# esphome-lg-pqrcuds0-rev1.net
KiCad netlist of a schematic drawn in EAGLE
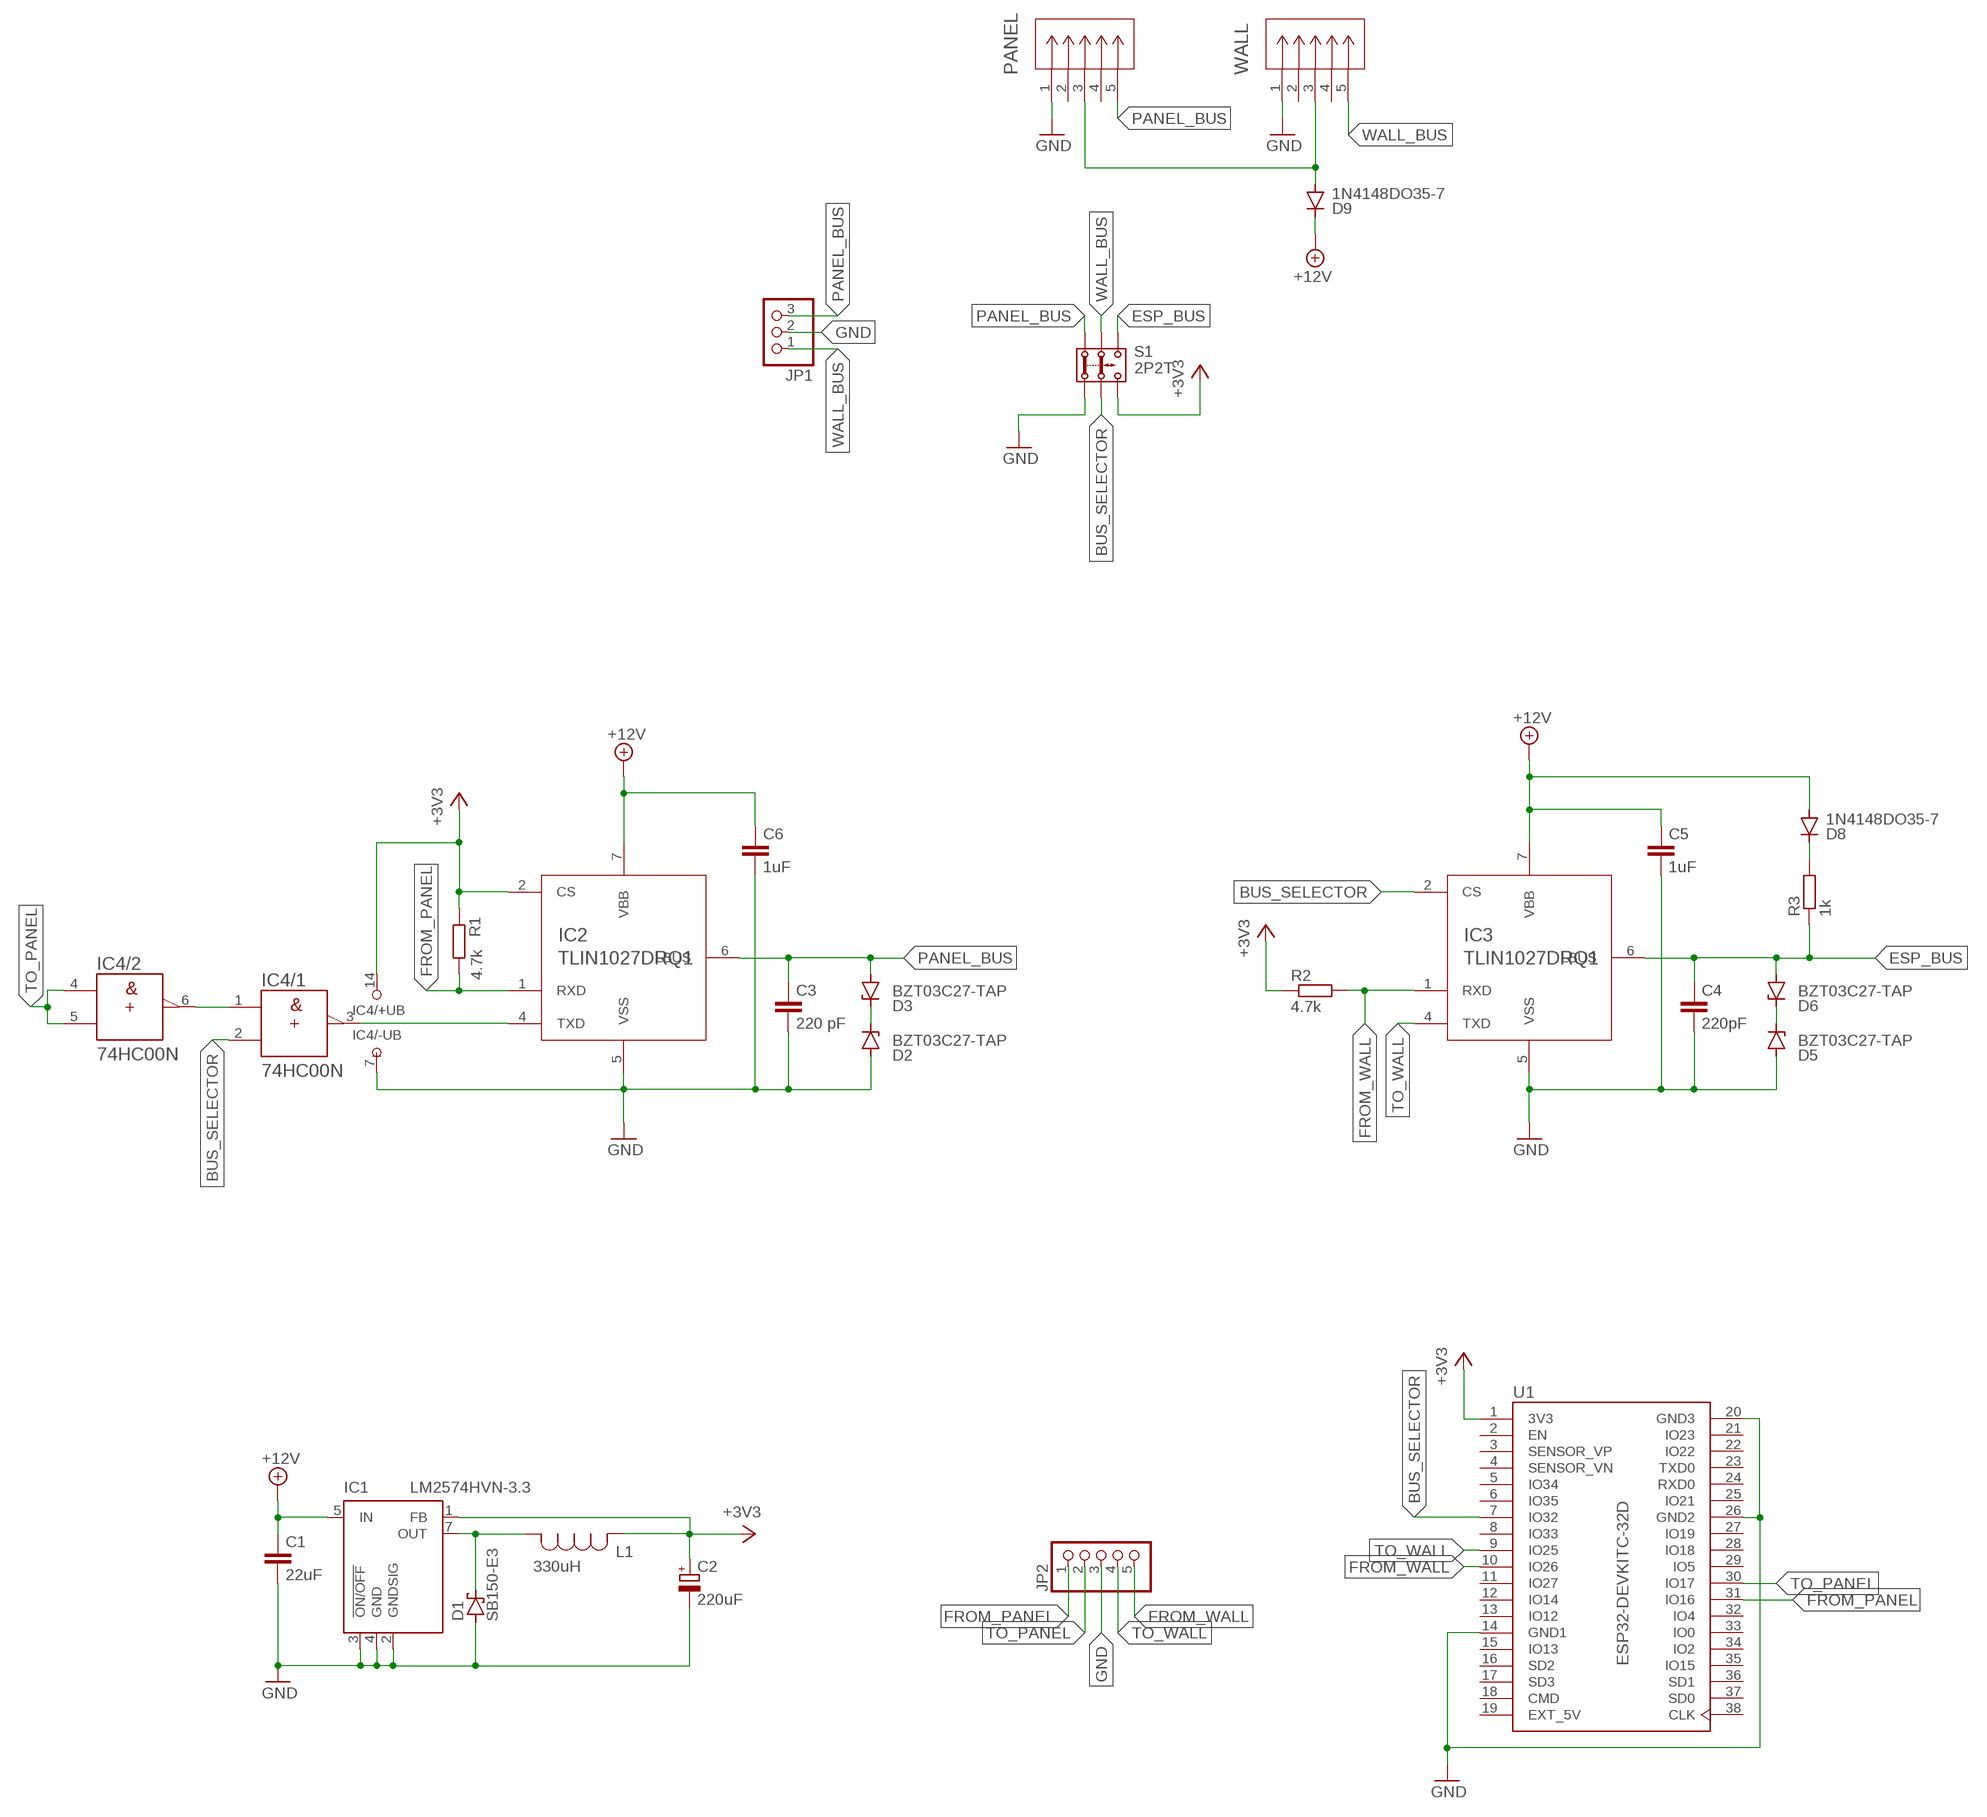
[diagram p0: schematic, sheet 1]

(export (version "E")
  (design (tool "Eeschema 10.0.6"))
  (components
    (comp (ref "C1")
      (value "22uF")
      (footprint "eagle-import:C050-025X075")
      (libsource (lib "eagle-import") (part "C-EU050-025X075"))
    )
    (comp (ref "C2")
      (value "220uF")
      (footprint "eagle-import:E2,5-6E")
      (libsource (lib "eagle-import") (part "CPOL-EUE2,5-6E"))
    )
    (comp (ref "C3")
      (value "220 pF")
      (footprint "eagle-import:C050-025X075")
      (libsource (lib "eagle-import") (part "C-EU050-025X075"))
    )
    (comp (ref "C4")
      (value "220pF")
      (footprint "eagle-import:C050-025X075")
      (libsource (lib "eagle-import") (part "C-EU050-025X075"))
    )
    (comp (ref "C5")
      (value "1uF")
      (footprint "eagle-import:C050-025X075")
      (libsource (lib "eagle-import") (part "C-EU050-025X075"))
    )
    (comp (ref "C6")
      (value "1uF")
      (footprint "eagle-import:C050-025X075")
      (libsource (lib "eagle-import") (part "C-EU050-025X075"))
    )
    (comp (ref "D1")
      (value "SB150-E3")
      (footprint "eagle-import:DO35-7")
      (libsource (lib "eagle-import") (part "SCHOTTKY-DIODEDO35-7"))
    )
    (comp (ref "D2")
      (value "BZT03C27-TAP")
      (footprint "eagle-import:SOD57Z10")
      (libsource (lib "eagle-import") (part "ZENER-DIODESOD57-10"))
    )
    (comp (ref "D3")
      (value "BZT03C27-TAP")
      (footprint "eagle-import:SOD57Z10")
      (libsource (lib "eagle-import") (part "ZENER-DIODESOD57-10"))
    )
    (comp (ref "D5")
      (value "BZT03C27-TAP")
      (footprint "eagle-import:SOD57Z10")
      (libsource (lib "eagle-import") (part "ZENER-DIODESOD57-10"))
    )
    (comp (ref "D6")
      (value "BZT03C27-TAP")
      (footprint "eagle-import:SOD57Z10")
      (libsource (lib "eagle-import") (part "ZENER-DIODESOD57-10"))
    )
    (comp (ref "D8")
      (value "1N4148DO35-7")
      (footprint "eagle-import:DO35-7")
      (libsource (lib "eagle-import") (part "1N4148DO35-7"))
    )
    (comp (ref "D9")
      (value "1N4148DO35-7")
      (footprint "eagle-import:DO35-7")
      (libsource (lib "eagle-import") (part "1N4148DO35-7"))
    )
    (comp (ref "IC1")
      (value "LM2574HVN-3.3")
      (footprint "eagle-import:DIL08")
      (libsource (lib "eagle-import") (part "LM2574?-HVN3.3"))
    )
    (comp (ref "IC2")
      (value "TLIN1027DRQ1")
      (footprint "eagle-import:SOIC8")
      (libsource (lib "eagle-import") (part "TLIN1027DRQ1"))
    )
    (comp (ref "IC3")
      (value "TLIN1027DRQ1")
      (footprint "eagle-import:SOIC8")
      (libsource (lib "eagle-import") (part "TLIN1027DRQ1"))
    )
    (comp (ref "IC4")
      (value "74HC00N")
      (footprint "eagle-import:DIL14")
      (libsource (lib "eagle-import") (part "7400NHC"))
    )
    (comp (ref "JP1")
      (value "PINHD-1X3/90")
      (footprint "eagle-import:1X03_90")
      (libsource (lib "eagle-import") (part "PINHD-1X3/90"))
    )
    (comp (ref "JP2")
      (value "PINHD-1X5/90")
      (footprint "eagle-import:1X05_90")
      (libsource (lib "eagle-import") (part "PINHD-1X5/90"))
    )
    (comp (ref "L1")
      (value "330uH")
      (footprint "eagle-import:AIAP-02_ABR")
      (fields (field (name "MANUFACTURER_PART_NUMBER") "AIAP-02-331K"))
      (libsource (lib "eagle-import") (part "AIAP-02-331K"))
    )
    (comp (ref "PANEL")
      (value "S5B-ZR(LF)(SN)")
      (footprint "eagle-import:CONN_S5B-ZR_JST")
      (fields (field (name "COPYRIGHT") "Copyright (C) 2018 Accelerated Designs. All rights reserved"))
      (libsource (lib "eagle-import") (part "S5B-ZR(LF)(SN)"))
    )
    (comp (ref "R1")
      (value "4.7k")
      (footprint "eagle-import:0204_7")
      (libsource (lib "eagle-import") (part "R-EU_0204/7"))
    )
    (comp (ref "R2")
      (value "4.7k")
      (footprint "eagle-import:0204_7")
      (libsource (lib "eagle-import") (part "R-EU_0204/7"))
    )
    (comp (ref "R3")
      (value "1k")
      (footprint "eagle-import:0204_7")
      (libsource (lib "eagle-import") (part "R-EU_0204/7"))
    )
    (comp (ref "S1")
      (value "2P2T")
      (footprint "eagle-import:2P2T")
      (libsource (lib "eagle-import") (part "2P2T"))
    )
    (comp (ref "U1")
      (value "ESP32-DEVKITC-32D")
      (footprint "eagle-import:MODULE_ESP32-DEVKITC-32D")
      (fields (field (name "MF") "Espressif Systems"))
      (libsource (lib "eagle-import") (part "ESP32-DEVKITC-32D"))
    )
    (comp (ref "WALL")
      (value "S5B-ZR(LF)(SN)")
      (footprint "eagle-import:CONN_S5B-ZR_JST")
      (fields (field (name "COPYRIGHT") "Copyright (C) 2018 Accelerated Designs. All rights reserved"))
      (libsource (lib "eagle-import") (part "S5B-ZR(LF)(SN)"))
    )
  )
  (nets
    (net (code "1") (name "+3V3") (class "Default")
      (node (ref "C2") (pin "+") (pinfunction "+_+") (pintype "passive"))
      (node (ref "IC1") (pin "1") (pinfunction "FB_1") (pintype "input"))
      (node (ref "IC2") (pin "2") (pinfunction "CS_2") (pintype "input"))
      (node (ref "IC4") (pin "14") (pinfunction "+UB_14") (pintype "power_in"))
      (node (ref "L1") (pin "2") (pinfunction "2_2") (pintype "passive"))
      (node (ref "R1") (pin "1") (pinfunction "1_1") (pintype "passive"))
      (node (ref "R2") (pin "1") (pinfunction "1_1") (pintype "passive"))
      (node (ref "S1") (pin "3.2") (pinfunction "3.2_3.2") (pintype "passive"))
      (node (ref "U1") (pin "1") (pinfunction "3V3_1") (pintype "power_in"))
    )
    (net (code "2") (name "+12V") (class "Default")
      (node (ref "C1") (pin "1") (pinfunction "1_1") (pintype "passive"))
      (node (ref "C5") (pin "1") (pinfunction "1_1") (pintype "passive"))
      (node (ref "C6") (pin "1") (pinfunction "1_1") (pintype "passive"))
      (node (ref "D8") (pin "A") (pinfunction "A_A") (pintype "passive"))
      (node (ref "D9") (pin "C") (pinfunction "C_C") (pintype "passive"))
      (node (ref "IC1") (pin "5") (pinfunction "IN_5") (pintype "input"))
      (node (ref "IC2") (pin "7") (pinfunction "VBB_7") (pintype "power_in"))
      (node (ref "IC3") (pin "7") (pinfunction "VBB_7") (pintype "power_in"))
    )
    (net (code "3") (name "/EXT_5V") (class "Default")
      (node (ref "U1") (pin "19") (pinfunction "EXT_5V_19") (pintype "power_in"))
    )
    (net (code "4") (name "BUS_SELECTOR") (class "Default")
      (node (ref "IC3") (pin "2") (pinfunction "CS_2") (pintype "input"))
      (node (ref "IC4") (pin "2") (pinfunction "B_2") (pintype "input"))
      (node (ref "S1") (pin "2.2") (pinfunction "2.2_2.2") (pintype "passive"))
      (node (ref "U1") (pin "7") (pinfunction "IO32_7") (pintype "bidirectional"))
    )
    (net (code "5") (name "ESP_BUS") (class "Default")
      (node (ref "C4") (pin "1") (pinfunction "1_1") (pintype "passive"))
      (node (ref "D6") (pin "A") (pinfunction "A_A") (pintype "passive"))
      (node (ref "IC3") (pin "6") (pinfunction "LBUS_6") (pintype "bidirectional"))
      (node (ref "R3") (pin "1") (pinfunction "1_1") (pintype "passive"))
      (node (ref "S1") (pin "3.1") (pinfunction "3.1_3.1") (pintype "passive"))
    )
    (net (code "6") (name "FROM_PANEL") (class "Default")
      (node (ref "IC2") (pin "1") (pinfunction "RXD_1") (pintype "output"))
      (node (ref "JP2") (pin "1") (pinfunction "1_1") (pintype "passive"))
      (node (ref "R1") (pin "2") (pinfunction "2_2") (pintype "passive"))
      (node (ref "U1") (pin "31") (pinfunction "IO16_31") (pintype "bidirectional"))
    )
    (net (code "7") (name "FROM_WALL") (class "Default")
      (node (ref "IC3") (pin "1") (pinfunction "RXD_1") (pintype "output"))
      (node (ref "JP2") (pin "5") (pinfunction "5_5") (pintype "passive"))
      (node (ref "R2") (pin "2") (pinfunction "2_2") (pintype "passive"))
      (node (ref "U1") (pin "10") (pinfunction "IO26_10") (pintype "bidirectional"))
    )
    (net (code "8") (name "GND") (class "Default")
      (node (ref "C1") (pin "2") (pinfunction "2_2") (pintype "passive"))
      (node (ref "C2") (pin "-") (pinfunction "-_-") (pintype "passive"))
      (node (ref "C3") (pin "2") (pinfunction "2_2") (pintype "passive"))
      (node (ref "C4") (pin "2") (pinfunction "2_2") (pintype "passive"))
      (node (ref "C5") (pin "2") (pinfunction "2_2") (pintype "passive"))
      (node (ref "C6") (pin "2") (pinfunction "2_2") (pintype "passive"))
      (node (ref "D1") (pin "A") (pinfunction "A_A") (pintype "passive"))
      (node (ref "D2") (pin "A") (pinfunction "A_A") (pintype "passive"))
      (node (ref "D5") (pin "A") (pinfunction "A_A") (pintype "passive"))
      (node (ref "IC1") (pin "2") (pinfunction "GNDSIG_2") (pintype "input"))
      (node (ref "IC1") (pin "3") (pinfunction "~{ON/OFF}_3") (pintype "input"))
      (node (ref "IC1") (pin "4") (pinfunction "GND_4") (pintype "power_in"))
      (node (ref "IC2") (pin "5") (pinfunction "VSS_5") (pintype "power_in"))
      (node (ref "IC3") (pin "5") (pinfunction "VSS_5") (pintype "power_in"))
      (node (ref "IC4") (pin "7") (pinfunction "-UB_7") (pintype "power_in"))
      (node (ref "JP1") (pin "2") (pinfunction "2_2") (pintype "passive"))
      (node (ref "JP2") (pin "3") (pinfunction "3_3") (pintype "passive"))
      (node (ref "PANEL") (pin "1") (pinfunction "1_1") (pintype "passive"))
      (node (ref "S1") (pin "1.2") (pinfunction "1.2_1.2") (pintype "passive"))
      (node (ref "U1") (pin "14") (pinfunction "GND1_14") (pintype "power_in"))
      (node (ref "U1") (pin "20") (pinfunction "GND3_20") (pintype "power_in"))
      (node (ref "U1") (pin "26") (pinfunction "GND2_26") (pintype "power_in"))
      (node (ref "WALL") (pin "1") (pinfunction "1_1") (pintype "passive"))
    )
    (net (code "9") (name "Net-(D2-PadC)") (class "Default")
      (node (ref "D2") (pin "C") (pinfunction "C_C") (pintype "passive"))
      (node (ref "D3") (pin "C") (pinfunction "C_C") (pintype "passive"))
    )
    (net (code "10") (name "Net-(D5-PadC)") (class "Default")
      (node (ref "D5") (pin "C") (pinfunction "C_C") (pintype "passive"))
      (node (ref "D6") (pin "C") (pinfunction "C_C") (pintype "passive"))
    )
    (net (code "11") (name "Net-(D8-PadC)") (class "Default")
      (node (ref "D8") (pin "C") (pinfunction "C_C") (pintype "passive"))
      (node (ref "R3") (pin "2") (pinfunction "2_2") (pintype "passive"))
    )
    (net (code "12") (name "Net-(D9-PadA)") (class "Default")
      (node (ref "D9") (pin "A") (pinfunction "A_A") (pintype "passive"))
      (node (ref "PANEL") (pin "3") (pinfunction "3_3") (pintype "passive"))
      (node (ref "WALL") (pin "3") (pinfunction "3_3") (pintype "passive"))
    )
    (net (code "13") (name "Net-(IC1-OUT)") (class "Default")
      (node (ref "D1") (pin "C") (pinfunction "C_C") (pintype "passive"))
      (node (ref "IC1") (pin "7") (pinfunction "OUT_7") (pintype "passive"))
      (node (ref "L1") (pin "1") (pinfunction "1_1") (pintype "passive"))
    )
    (net (code "14") (name "Net-(IC2-TXD)") (class "Default")
      (node (ref "IC2") (pin "4") (pinfunction "TXD_4") (pintype "input"))
      (node (ref "IC4") (pin "3") (pinfunction "Y_3") (pintype "output"))
    )
    (net (code "15") (name "Net-(IC4C-A)") (class "Default")
      (node (ref "IC4") (pin "1") (pinfunction "A_1") (pintype "input"))
      (node (ref "IC4") (pin "6") (pinfunction "Y_6") (pintype "output"))
    )
    (net (code "16") (name "PANEL_BUS") (class "Default")
      (node (ref "C3") (pin "1") (pinfunction "1_1") (pintype "passive"))
      (node (ref "D3") (pin "A") (pinfunction "A_A") (pintype "passive"))
      (node (ref "IC2") (pin "6") (pinfunction "LBUS_6") (pintype "bidirectional"))
      (node (ref "JP1") (pin "3") (pinfunction "3_3") (pintype "passive"))
      (node (ref "PANEL") (pin "5") (pinfunction "5_5") (pintype "passive"))
      (node (ref "S1") (pin "1.1") (pinfunction "1.1_1.1") (pintype "passive"))
    )
    (net (code "17") (name "TO_PANEL") (class "Default")
      (node (ref "IC4") (pin "4") (pinfunction "A_4") (pintype "input"))
      (node (ref "IC4") (pin "5") (pinfunction "B_5") (pintype "input"))
      (node (ref "JP2") (pin "2") (pinfunction "2_2") (pintype "passive"))
      (node (ref "U1") (pin "30") (pinfunction "IO17_30") (pintype "bidirectional"))
    )
    (net (code "18") (name "TO_WALL") (class "Default")
      (node (ref "IC3") (pin "4") (pinfunction "TXD_4") (pintype "input"))
      (node (ref "JP2") (pin "4") (pinfunction "4_4") (pintype "passive"))
      (node (ref "U1") (pin "9") (pinfunction "IO25_9") (pintype "bidirectional"))
    )
    (net (code "19") (name "WALL_BUS") (class "Default")
      (node (ref "JP1") (pin "1") (pinfunction "1_1") (pintype "passive"))
      (node (ref "S1") (pin "2.1") (pinfunction "2.1_2.1") (pintype "passive"))
      (node (ref "WALL") (pin "5") (pinfunction "5_5") (pintype "passive"))
    )
    (net (code "20") (name "unconnected-(PANEL-Pad2)") (class "Default")
      (node (ref "PANEL") (pin "2") (pinfunction "2_2") (pintype "passive"))
    )
    (net (code "21") (name "unconnected-(PANEL-Pad4)") (class "Default")
      (node (ref "PANEL") (pin "4") (pinfunction "4_4") (pintype "passive"))
    )
    (net (code "22") (name "unconnected-(U1-CLK-Pad38)") (class "Default")
      (node (ref "U1") (pin "38") (pinfunction "CLK_38") (pintype "input"))
    )
    (net (code "23") (name "unconnected-(U1-CMD-Pad18)") (class "Default")
      (node (ref "U1") (pin "18") (pinfunction "CMD_18") (pintype "bidirectional"))
    )
    (net (code "24") (name "unconnected-(U1-EN-Pad2)") (class "Default")
      (node (ref "U1") (pin "2") (pinfunction "EN_2") (pintype "input"))
    )
    (net (code "25") (name "unconnected-(U1-IO0-Pad33)") (class "Default")
      (node (ref "U1") (pin "33") (pinfunction "IO0_33") (pintype "bidirectional"))
    )
    (net (code "26") (name "unconnected-(U1-IO2-Pad34)") (class "Default")
      (node (ref "U1") (pin "34") (pinfunction "IO2_34") (pintype "bidirectional"))
    )
    (net (code "27") (name "unconnected-(U1-IO4-Pad32)") (class "Default")
      (node (ref "U1") (pin "32") (pinfunction "IO4_32") (pintype "bidirectional"))
    )
    (net (code "28") (name "unconnected-(U1-IO5-Pad29)") (class "Default")
      (node (ref "U1") (pin "29") (pinfunction "IO5_29") (pintype "bidirectional"))
    )
    (net (code "29") (name "unconnected-(U1-IO12-Pad13)") (class "Default")
      (node (ref "U1") (pin "13") (pinfunction "IO12_13") (pintype "bidirectional"))
    )
    (net (code "30") (name "unconnected-(U1-IO13-Pad15)") (class "Default")
      (node (ref "U1") (pin "15") (pinfunction "IO13_15") (pintype "bidirectional"))
    )
    (net (code "31") (name "unconnected-(U1-IO14-Pad12)") (class "Default")
      (node (ref "U1") (pin "12") (pinfunction "IO14_12") (pintype "bidirectional"))
    )
    (net (code "32") (name "unconnected-(U1-IO15-Pad35)") (class "Default")
      (node (ref "U1") (pin "35") (pinfunction "IO15_35") (pintype "bidirectional"))
    )
    (net (code "33") (name "unconnected-(U1-IO18-Pad28)") (class "Default")
      (node (ref "U1") (pin "28") (pinfunction "IO18_28") (pintype "bidirectional"))
    )
    (net (code "34") (name "unconnected-(U1-IO19-Pad27)") (class "Default")
      (node (ref "U1") (pin "27") (pinfunction "IO19_27") (pintype "bidirectional"))
    )
    (net (code "35") (name "unconnected-(U1-IO21-Pad25)") (class "Default")
      (node (ref "U1") (pin "25") (pinfunction "IO21_25") (pintype "bidirectional"))
    )
    (net (code "36") (name "unconnected-(U1-IO22-Pad22)") (class "Default")
      (node (ref "U1") (pin "22") (pinfunction "IO22_22") (pintype "bidirectional"))
    )
    (net (code "37") (name "unconnected-(U1-IO23-Pad21)") (class "Default")
      (node (ref "U1") (pin "21") (pinfunction "IO23_21") (pintype "bidirectional"))
    )
    (net (code "38") (name "unconnected-(U1-IO27-Pad11)") (class "Default")
      (node (ref "U1") (pin "11") (pinfunction "IO27_11") (pintype "bidirectional"))
    )
    (net (code "39") (name "unconnected-(U1-IO33-Pad8)") (class "Default")
      (node (ref "U1") (pin "8") (pinfunction "IO33_8") (pintype "bidirectional"))
    )
    (net (code "40") (name "unconnected-(U1-IO34-Pad5)") (class "Default")
      (node (ref "U1") (pin "5") (pinfunction "IO34_5") (pintype "bidirectional"))
    )
    (net (code "41") (name "unconnected-(U1-IO35-Pad6)") (class "Default")
      (node (ref "U1") (pin "6") (pinfunction "IO35_6") (pintype "bidirectional"))
    )
    (net (code "42") (name "unconnected-(U1-RXD0-Pad24)") (class "Default")
      (node (ref "U1") (pin "24") (pinfunction "RXD0_24") (pintype "input"))
    )
    (net (code "43") (name "unconnected-(U1-SD0-Pad37)") (class "Default")
      (node (ref "U1") (pin "37") (pinfunction "SD0_37") (pintype "bidirectional"))
    )
    (net (code "44") (name "unconnected-(U1-SD1-Pad36)") (class "Default")
      (node (ref "U1") (pin "36") (pinfunction "SD1_36") (pintype "bidirectional"))
    )
    (net (code "45") (name "unconnected-(U1-SD2-Pad16)") (class "Default")
      (node (ref "U1") (pin "16") (pinfunction "SD2_16") (pintype "bidirectional"))
    )
    (net (code "46") (name "unconnected-(U1-SD3-Pad17)") (class "Default")
      (node (ref "U1") (pin "17") (pinfunction "SD3_17") (pintype "bidirectional"))
    )
    (net (code "47") (name "unconnected-(U1-SENSOR_VN-Pad4)") (class "Default")
      (node (ref "U1") (pin "4") (pinfunction "SENSOR_VN_4") (pintype "input"))
    )
    (net (code "48") (name "unconnected-(U1-SENSOR_VP-Pad3)") (class "Default")
      (node (ref "U1") (pin "3") (pinfunction "SENSOR_VP_3") (pintype "input"))
    )
    (net (code "49") (name "unconnected-(U1-TXD0-Pad23)") (class "Default")
      (node (ref "U1") (pin "23") (pinfunction "TXD0_23") (pintype "output"))
    )
    (net (code "50") (name "unconnected-(WALL-Pad2)") (class "Default")
      (node (ref "WALL") (pin "2") (pinfunction "2_2") (pintype "passive"))
    )
    (net (code "51") (name "unconnected-(WALL-Pad4)") (class "Default")
      (node (ref "WALL") (pin "4") (pinfunction "4_4") (pintype "passive"))
    )
  )
)
